# 6_Current_Sensing.net
KiCad netlist of a schematic drawn in Altium Designer
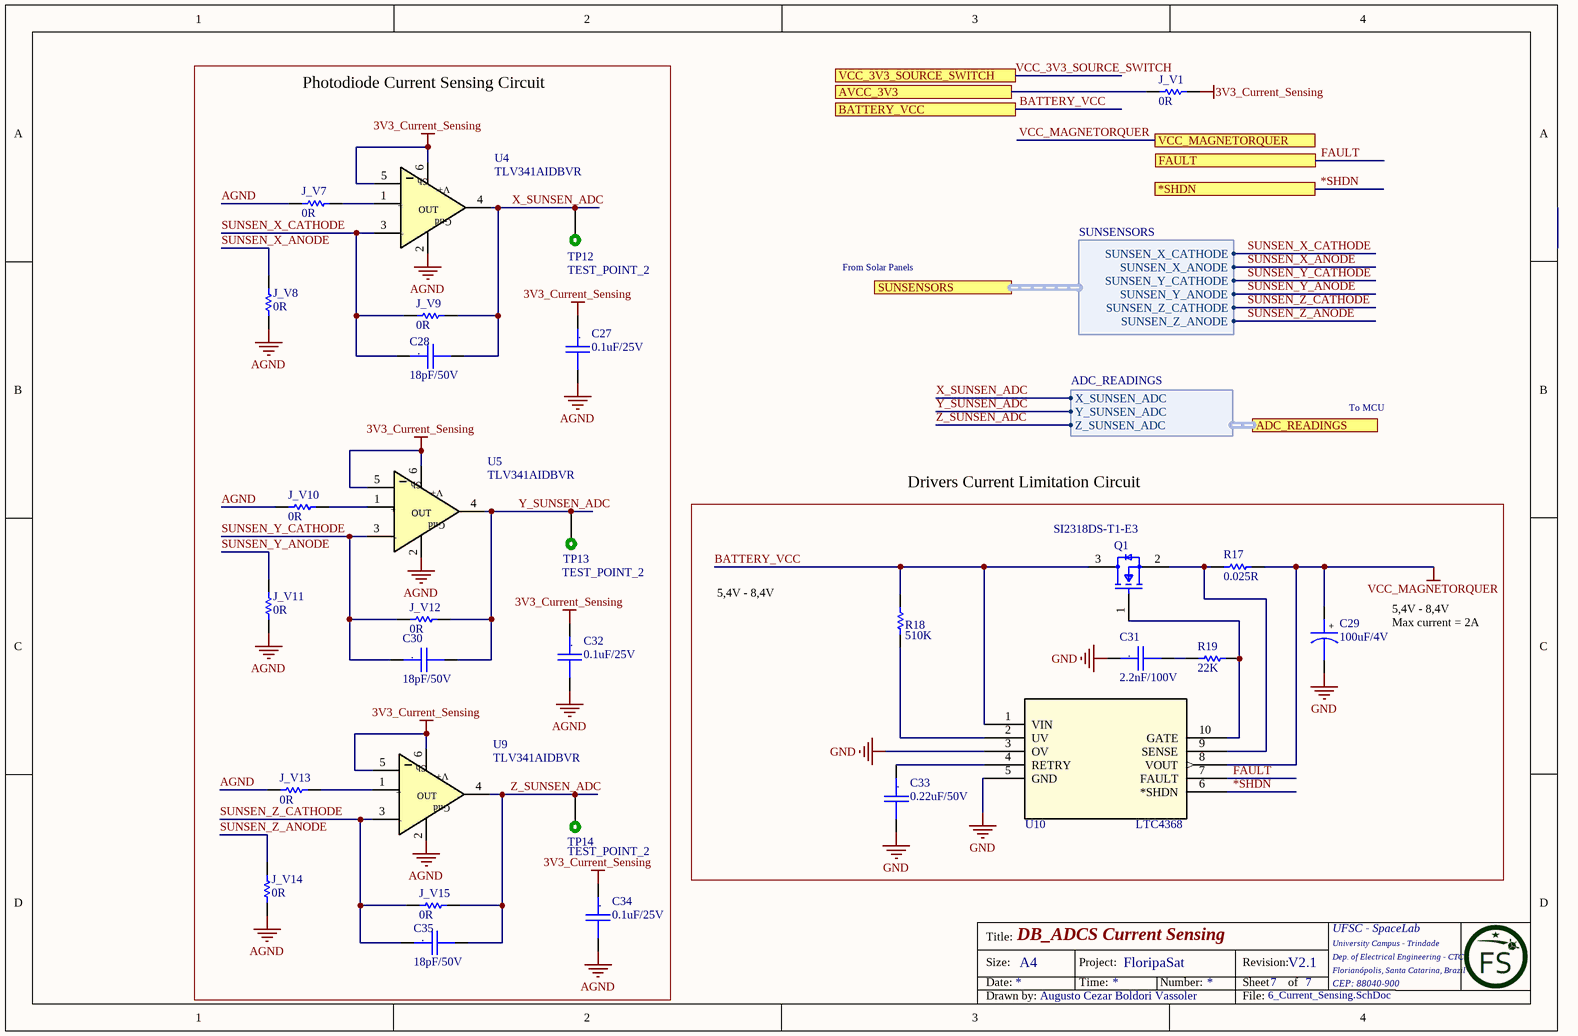
[diagram p0: 6_Current_Sensing.SchDoc]

(export (version "E")
  (design (tool "Eeschema 10.0.6"))
  (components
    (comp (ref "C27")
      (value "0.1uF/25V")
      (footprint "CC0805")
      (description "CAP CER 0.1UF 25V 10% X7R 0805")
      (fields (field (name "PARTNUMBER") "CC0805KRX7R8BB104"))
      (libsource (lib "PCB_Eng_Model_OBDH_2") (part "Cap_Cer_X7R_0.1uF_25V_0805"))
    )
    (comp (ref "C28")
      (value "18pF/50V")
      (footprint "CC0805")
      (description "CAP CER 18pF 50V 5% X7R 0805")
      (fields (field (name "PARTNUMBER") "CC0805JRNPO9BN180"))
      (libsource (lib "PCB_Eng_Model_OBDH_2") (part "Cap_Cer_X7R_18pF_50V_0805"))
    )
    (comp (ref "C29")
      (value "100uF/4V")
      (footprint "CC0805_Tantalum")
      (description "CAP TANT 100UF 4V 20% 0805")
      (fields
        (field (name "MANUFACTURER") "Kyocera AVX")
        (field (name "MANUFACTURER PART NUMBER") "TACR107M004RTA")
      )
      (libsource (lib "PCB_Eng_Model_OBDH_2") (part "Cap_Tant_SMD_100uF_4V_0805"))
    )
    (comp (ref "C30")
      (value "18pF/50V")
      (footprint "CC0805")
      (description "CAP CER 18pF 50V 5% X7R 0805")
      (fields (field (name "PARTNUMBER") "CC0805JRNPO9BN180"))
      (libsource (lib "PCB_Eng_Model_OBDH_2") (part "Cap_Cer_X7R_18pF_50V_0805"))
    )
    (comp (ref "C31")
      (value "2.2nF/100V")
      (footprint "CC0805")
      (description "Cap Cer 0.0022uF 100V X7R 5% 0805")
      (fields
        (field (name "MANUFACTURER") "Kyocera AVX")
        (field (name "MANUFACTURER PART NUMBER") "08051C222JAT2A")
      )
      (libsource (lib "PCB_Eng_Model_OBDH_2") (part "Cap_Cer_X7R_0.0022uF_0805"))
    )
    (comp (ref "C32")
      (value "0.1uF/25V")
      (footprint "CC0805")
      (description "CAP CER 0.1UF 25V 10% X7R 0805")
      (fields (field (name "PARTNUMBER") "CC0805KRX7R8BB104"))
      (libsource (lib "PCB_Eng_Model_OBDH_2") (part "Cap_Cer_X7R_0.1uF_25V_0805"))
    )
    (comp (ref "C33")
      (value "0.22uF/50V")
      (footprint "CC0805")
      (description "CAP CER 0.22UF 50V X7R 0805")
      (fields
        (field (name "MANUFACTURER") "KEMET")
        (field (name "MANUFACTURER PART NUMBER") "C0805C224K5RACTU")
      )
      (libsource (lib "PCB_Eng_Model_OBDH_2") (part "Cap_Cer_X7R_0.22uF_0805"))
    )
    (comp (ref "C34")
      (value "0.1uF/25V")
      (footprint "CC0805")
      (description "CAP CER 0.1UF 25V 10% X7R 0805")
      (fields (field (name "PARTNUMBER") "CC0805KRX7R8BB104"))
      (libsource (lib "PCB_Eng_Model_OBDH_2") (part "Cap_Cer_X7R_0.1uF_25V_0805"))
    )
    (comp (ref "C35")
      (value "18pF/50V")
      (footprint "CC0805")
      (description "CAP CER 18pF 50V 5% X7R 0805")
      (fields (field (name "PARTNUMBER") "CC0805JRNPO9BN180"))
      (libsource (lib "PCB_Eng_Model_OBDH_2") (part "Cap_Cer_X7R_18pF_50V_0805"))
    )
    (comp (ref "J_V1")
      (value "0R")
      (footprint "PCB_OBDH:0805")
      (description "RES 0R OHM 1/16W JUMPER 0805")
      (fields (field (name "PARTNUMBER") "CRCW08050000Z0EA"))
      (libsource (lib "PCB_DB_ADCS") (part "R0R_JUMPER_1/16W_0805"))
    )
    (comp (ref "J_V7")
      (value "0R")
      (footprint "0805-LED")
      (description "RES 0R OHM 1/16W JUMPER 0805")
      (fields (field (name "PARTNUMBER") "CRCW08050000Z0EA"))
      (libsource (lib "PCB_Eng_Model_OBDH_2") (part "R0R_JUMPER_1/16W_0805"))
    )
    (comp (ref "J_V8")
      (value "0R")
      (footprint "0805-LED")
      (description "RES 0R OHM 1/16W JUMPER 0805")
      (fields (field (name "PARTNUMBER") "CRCW08050000Z0EA"))
      (libsource (lib "PCB_Eng_Model_OBDH_2") (part "R0R_JUMPER_1/16W_0805"))
    )
    (comp (ref "J_V9")
      (value "0R")
      (footprint "0805-LED")
      (description "RES 0R OHM 1/16W JUMPER 0805")
      (fields (field (name "PARTNUMBER") "CRCW08050000Z0EA"))
      (libsource (lib "PCB_Eng_Model_OBDH_2") (part "R0R_JUMPER_1/16W_0805"))
    )
    (comp (ref "J_V10")
      (value "0R")
      (footprint "0805-LED")
      (description "RES 0R OHM 1/16W JUMPER 0805")
      (fields (field (name "PARTNUMBER") "CRCW08050000Z0EA"))
      (libsource (lib "PCB_Eng_Model_OBDH_2") (part "R0R_JUMPER_1/16W_0805"))
    )
    (comp (ref "J_V11")
      (value "0R")
      (footprint "0805-LED")
      (description "RES 0R OHM 1/16W JUMPER 0805")
      (fields (field (name "PARTNUMBER") "CRCW08050000Z0EA"))
      (libsource (lib "PCB_Eng_Model_OBDH_2") (part "R0R_JUMPER_1/16W_0805"))
    )
    (comp (ref "J_V12")
      (value "0R")
      (footprint "0805-LED")
      (description "RES 0R OHM 1/16W JUMPER 0805")
      (fields (field (name "PARTNUMBER") "CRCW08050000Z0EA"))
      (libsource (lib "PCB_Eng_Model_OBDH_2") (part "R0R_JUMPER_1/16W_0805"))
    )
    (comp (ref "J_V13")
      (value "0R")
      (footprint "0805-LED")
      (description "RES 0R OHM 1/16W JUMPER 0805")
      (fields (field (name "PARTNUMBER") "CRCW08050000Z0EA"))
      (libsource (lib "PCB_Eng_Model_OBDH_2") (part "R0R_JUMPER_1/16W_0805"))
    )
    (comp (ref "J_V14")
      (value "0R")
      (footprint "0805-LED")
      (description "RES 0R OHM 1/16W JUMPER 0805")
      (fields (field (name "PARTNUMBER") "CRCW08050000Z0EA"))
      (libsource (lib "PCB_Eng_Model_OBDH_2") (part "R0R_JUMPER_1/16W_0805"))
    )
    (comp (ref "J_V15")
      (value "0R")
      (footprint "0805-LED")
      (description "RES 0R OHM 1/16W JUMPER 0805")
      (fields (field (name "PARTNUMBER") "CRCW08050000Z0EA"))
      (libsource (lib "PCB_Eng_Model_OBDH_2") (part "R0R_JUMPER_1/16W_0805"))
    )
    (comp (ref "Q1")
      (value "SI2318DS-T1-E3")
      (footprint "FP-S-03946-MFG")
      (description "MOSFET N-CH 40V 3A SOT23-3")
      (fields
        (field (name "MANUFACTURER") "Vishay")
        (field (name "OCTOPART") "https://octopart.com/si2318ds-t1-e3-vishay-40866469")
      )
      (libsource (lib "PCB_DB_ADCS") (part "CMP-02550-000015-1"))
    )
    (comp (ref "R17")
      (value "0.025R")
      (footprint "1206")
      (description "RES 0.025 OHM - 0.25W 1% 1206")
      (fields
        (field (name "MANUFACTURER") "Vishay Dale")
        (field (name "MANUFACTURER PART NUMBER") "WSL1206R0250FBA")
      )
      (libsource (lib "PCB_Eng_Model_OBDH_2") (part "R0.025_1%_1/4W_1206"))
    )
    (comp (ref "R18")
      (value "510K")
      (footprint "0805")
      (description "RES 510K OHM 1/8W 1% 0805")
      (fields
        (field (name "MANUFACTURER") "Vishay")
        (field (name "MANUFACTURER PART NUMBER") "CRCW0805510KFKEA")
      )
      (libsource (lib "PCB_Eng_Model_OBDH_2") (part "R510K_1%_1/8W_0805"))
    )
    (comp (ref "R19")
      (value "22K")
      (footprint "0805-LED")
      (description "RES 22K OHM 1.25W 1% 0805")
      (fields
        (field (name "MANUFACTURER") "Vishay")
        (field (name "MANUFACTURER PART NUMBER") "CRCW080522K0FKEA")
      )
      (libsource (lib "PCB_Eng_Model_OBDH_2") (part "R22K_1%_1.25W_0805"))
    )
    (comp (ref "TP12")
      (value "TEST_POINT_2")
      (footprint "TEST_POINT_2")
      (description "Test point")
      (libsource (lib "PCB_Eng_Model_OBDH_2") (part "TEST_POINT_2"))
    )
    (comp (ref "TP13")
      (value "TEST_POINT_2")
      (footprint "TEST_POINT_2")
      (description "Test point")
      (libsource (lib "PCB_Eng_Model_OBDH_2") (part "TEST_POINT_2"))
    )
    (comp (ref "TP14")
      (value "TEST_POINT_2")
      (footprint "TEST_POINT_2")
      (description "Test point")
      (libsource (lib "PCB_Eng_Model_OBDH_2") (part "TEST_POINT_2"))
    )
    (comp (ref "U4")
      (value "TLV341AIDBVR")
      (footprint "SOT-23 6L")
      (libsource (lib "PCB_Eng_Model_OBDH_2") (part "TLV341AIDBVR"))
    )
    (comp (ref "U5")
      (value "TLV341AIDBVR")
      (footprint "SOT-23 6L")
      (libsource (lib "PCB_Eng_Model_OBDH_2") (part "TLV341AIDBVR"))
    )
    (comp (ref "U9")
      (value "TLV341AIDBVR")
      (footprint "SOT-23 6L")
      (libsource (lib "") (part "TLV341AIDBVR_1"))
    )
    (comp (ref "U10")
      (value "LTC4368")
      (footprint "MSOP-10_MS")
      (description "LTC4368 - 100V UV/OV and Reverse Protection Controller with Bidirectional Circuit Breaker")
      (fields
        (field (name "MANUFACTURER") "Analog Devices")
        (field (name "MANUFACTURER PART NUMBER") "LTC4368IMS-2#PBF")
      )
      (libsource (lib "PCB_Eng_Model_OBDH_2") (part "LTC4368"))
    )
  )
  (nets
    (net (code "3") (name "/*SHDN") (class "Default")
      (node (ref "U10") (pin "6") (pinfunction "*SHDN_6") (pintype "passive"))
    )
    (net (code "4") (name "/AVCC_3V3") (class "Default")
      (node (ref "J_V1") (pin "2") (pinfunction "2_2") (pintype "passive"))
    )
    (net (code "5") (name "/BATTERY_VCC") (class "Default")
      (node (ref "Q1") (pin "3") (pinfunction "D_3") (pintype "passive"))
      (node (ref "R18") (pin "1") (pinfunction "1_1") (pintype "passive"))
      (node (ref "U10") (pin "1") (pinfunction "VIN_1") (pintype "passive"))
    )
    (net (code "6") (name "/FAULT") (class "Default")
      (node (ref "U10") (pin "7") (pinfunction "FAULT_7") (pintype "passive"))
    )
    (net (code "7") (name "/SUNSEN_X_ANODE") (class "Default")
      (node (ref "J_V8") (pin "2") (pinfunction "2_2") (pintype "passive"))
    )
    (net (code "8") (name "/SUNSEN_X_CATHODE") (class "Default")
      (node (ref "C28") (pin "1") (pinfunction "1_1") (pintype "passive"))
      (node (ref "J_V9") (pin "2") (pinfunction "2_2") (pintype "passive"))
      (node (ref "U4") (pin "3") (pinfunction "-IN_3") (pintype "passive"))
    )
    (net (code "9") (name "/SUNSEN_Y_ANODE") (class "Default")
      (node (ref "J_V11") (pin "1") (pinfunction "1_1") (pintype "passive"))
    )
    (net (code "10") (name "/SUNSEN_Y_CATHODE") (class "Default")
      (node (ref "C30") (pin "1") (pinfunction "1_1") (pintype "passive"))
      (node (ref "J_V12") (pin "2") (pinfunction "2_2") (pintype "passive"))
      (node (ref "U5") (pin "3") (pinfunction "-IN_3") (pintype "passive"))
    )
    (net (code "11") (name "/SUNSEN_Z_ANODE") (class "Default")
      (node (ref "J_V14") (pin "1") (pinfunction "1_1") (pintype "passive"))
    )
    (net (code "12") (name "/SUNSEN_Z_CATHODE") (class "Default")
      (node (ref "C35") (pin "1") (pinfunction "1_1") (pintype "passive"))
      (node (ref "J_V15") (pin "2") (pinfunction "2_2") (pintype "passive"))
      (node (ref "U9") (pin "3") (pinfunction "-IN_3") (pintype "passive"))
    )
    (net (code "14") (name "/X_SUNSEN_ADC") (class "Default")
      (node (ref "C28") (pin "2") (pinfunction "2_2") (pintype "passive"))
      (node (ref "J_V9") (pin "1") (pinfunction "1_1") (pintype "passive"))
      (node (ref "TP12") (pin "1") (pinfunction "1_1") (pintype "passive"))
      (node (ref "U4") (pin "4") (pinfunction "OUT_4") (pintype "passive"))
    )
    (net (code "15") (name "/Y_SUNSEN_ADC") (class "Default")
      (node (ref "C30") (pin "2") (pinfunction "2_2") (pintype "passive"))
      (node (ref "J_V12") (pin "1") (pinfunction "1_1") (pintype "passive"))
      (node (ref "TP13") (pin "1") (pinfunction "1_1") (pintype "passive"))
      (node (ref "U5") (pin "4") (pinfunction "OUT_4") (pintype "passive"))
    )
    (net (code "16") (name "/Z_SUNSEN_ADC") (class "Default")
      (node (ref "C35") (pin "2") (pinfunction "2_2") (pintype "passive"))
      (node (ref "J_V15") (pin "1") (pinfunction "1_1") (pintype "passive"))
      (node (ref "TP14") (pin "1") (pinfunction "1_1") (pintype "passive"))
      (node (ref "U9") (pin "4") (pinfunction "OUT_4") (pintype "passive"))
    )
    (net (code "19") (name "3V3_Current_Sensing") (class "Default")
      (node (ref "C27") (pin "1") (pinfunction "1_1") (pintype "passive"))
      (node (ref "C32") (pin "1") (pinfunction "1_1") (pintype "passive"))
      (node (ref "C34") (pin "1") (pinfunction "1_1") (pintype "passive"))
      (node (ref "J_V1") (pin "1") (pinfunction "1_1") (pintype "passive"))
      (node (ref "U4") (pin "5") (pinfunction "EN_5") (pintype "passive"))
      (node (ref "U4") (pin "6") (pinfunction "V+_6") (pintype "passive"))
      (node (ref "U5") (pin "5") (pinfunction "EN_5") (pintype "passive"))
      (node (ref "U5") (pin "6") (pinfunction "V+_6") (pintype "passive"))
      (node (ref "U9") (pin "5") (pinfunction "EN_5") (pintype "passive"))
      (node (ref "U9") (pin "6") (pinfunction "V+_6") (pintype "passive"))
    )
    (net (code "20") (name "AGND") (class "Default")
      (node (ref "C27") (pin "2") (pinfunction "2_2") (pintype "passive"))
      (node (ref "C32") (pin "2") (pinfunction "2_2") (pintype "passive"))
      (node (ref "C34") (pin "2") (pinfunction "2_2") (pintype "passive"))
      (node (ref "J_V10") (pin "2") (pinfunction "2_2") (pintype "passive"))
      (node (ref "J_V11") (pin "2") (pinfunction "2_2") (pintype "passive"))
      (node (ref "J_V13") (pin "2") (pinfunction "2_2") (pintype "passive"))
      (node (ref "J_V14") (pin "2") (pinfunction "2_2") (pintype "passive"))
      (node (ref "J_V7") (pin "2") (pinfunction "2_2") (pintype "passive"))
      (node (ref "J_V8") (pin "1") (pinfunction "1_1") (pintype "passive"))
      (node (ref "U4") (pin "2") (pinfunction "Gnd_2") (pintype "passive"))
      (node (ref "U5") (pin "2") (pinfunction "Gnd_2") (pintype "passive"))
      (node (ref "U9") (pin "2") (pinfunction "Gnd_2") (pintype "passive"))
    )
    (net (code "21") (name "GND") (class "Default")
      (node (ref "C29") (pin "2") (pinfunction "2_2") (pintype "passive"))
      (node (ref "C31") (pin "1") (pinfunction "1_1") (pintype "passive"))
      (node (ref "C33") (pin "2") (pinfunction "2_2") (pintype "passive"))
      (node (ref "U10") (pin "3") (pinfunction "OV_3") (pintype "passive"))
      (node (ref "U10") (pin "5") (pinfunction "GND_5") (pintype "passive"))
    )
    (net (code "22") (name "Net-(C31-Pad2)") (class "Default")
      (node (ref "C31") (pin "2") (pinfunction "2_2") (pintype "passive"))
      (node (ref "R19") (pin "2") (pinfunction "2_2") (pintype "passive"))
    )
    (net (code "23") (name "Net-(Q1-G)") (class "Default")
      (node (ref "Q1") (pin "1") (pinfunction "G_1") (pintype "passive"))
      (node (ref "R19") (pin "1") (pinfunction "1_1") (pintype "passive"))
      (node (ref "U10") (pin "10") (pinfunction "GATE_10") (pintype "passive"))
    )
    (net (code "24") (name "Net-(Q1-S)") (class "Default")
      (node (ref "Q1") (pin "2") (pinfunction "S_2") (pintype "passive"))
      (node (ref "R17") (pin "2") (pinfunction "2_2") (pintype "passive"))
      (node (ref "U10") (pin "9") (pinfunction "SENSE_9") (pintype "passive"))
    )
    (net (code "25") (name "Net-(U4-+IN)") (class "Default")
      (node (ref "J_V7") (pin "1") (pinfunction "1_1") (pintype "passive"))
      (node (ref "U4") (pin "1") (pinfunction "+IN_1") (pintype "passive"))
    )
    (net (code "26") (name "Net-(U5-+IN)") (class "Default")
      (node (ref "J_V10") (pin "1") (pinfunction "1_1") (pintype "passive"))
      (node (ref "U5") (pin "1") (pinfunction "+IN_1") (pintype "passive"))
    )
    (net (code "27") (name "Net-(U9-+IN)") (class "Default")
      (node (ref "J_V13") (pin "1") (pinfunction "1_1") (pintype "passive"))
      (node (ref "U9") (pin "1") (pinfunction "+IN_1") (pintype "passive"))
    )
    (net (code "28") (name "Net-(U10-RETRY)") (class "Default")
      (node (ref "C33") (pin "1") (pinfunction "1_1") (pintype "passive"))
      (node (ref "U10") (pin "4") (pinfunction "RETRY_4") (pintype "passive"))
    )
    (net (code "29") (name "Net-(U10-UV)") (class "Default")
      (node (ref "R18") (pin "2") (pinfunction "2_2") (pintype "passive"))
      (node (ref "U10") (pin "2") (pinfunction "UV_2") (pintype "passive"))
    )
    (net (code "30") (name "VCC_MAGNETORQUER") (class "Default")
      (node (ref "C29") (pin "1") (pinfunction "1_1") (pintype "passive"))
      (node (ref "R17") (pin "1") (pinfunction "1_1") (pintype "passive"))
      (node (ref "U10") (pin "8") (pinfunction "VOUT_8") (pintype "output"))
    )
  )
)
